# design.net
KiCad netlist of a schematic drawn in Altium Designer
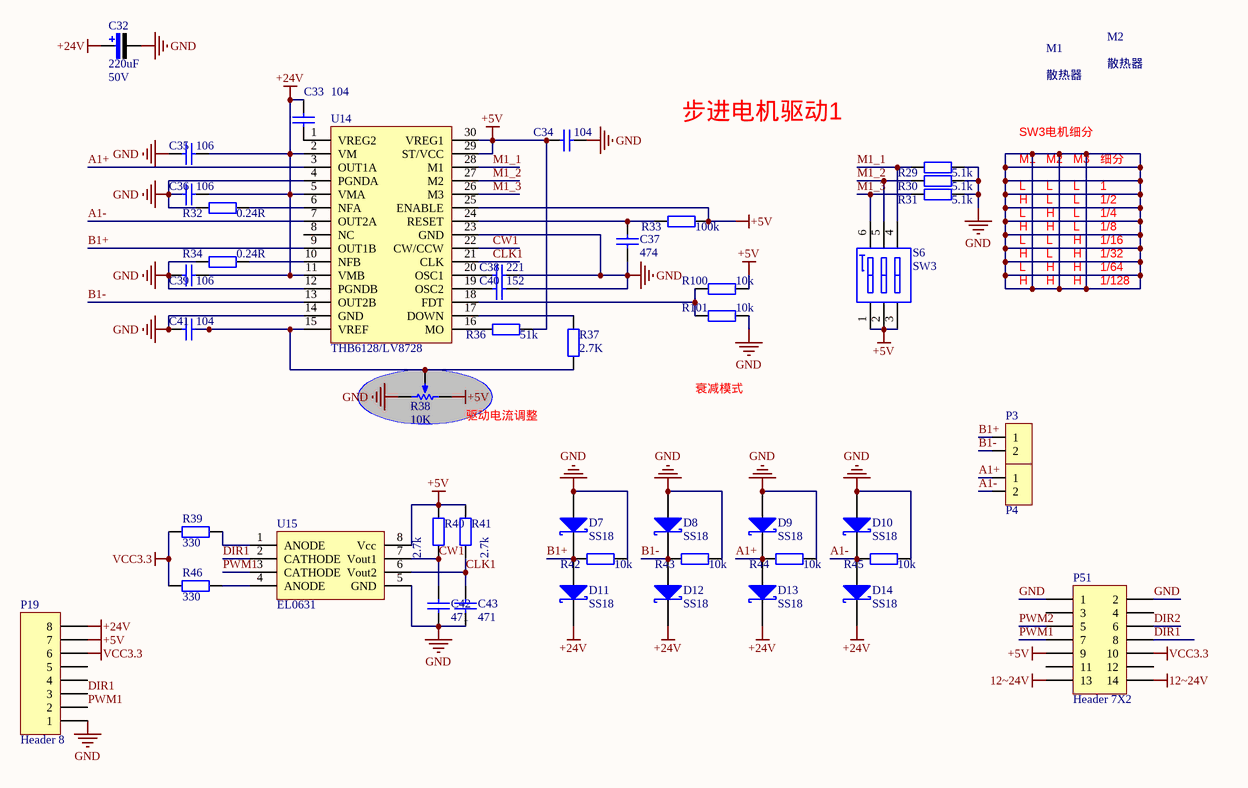
[diagram p0: 搅拌驱动驱动.SchDoc]

(export (version "E")
  (design (tool "Eeschema 10.0.6"))
  (components
    (comp (ref "C32")
      (value "220uF")
      (footprint "C-RB-S10")
      (description "极性电解电容")
      (fields
        (field (name "VOL") "50V")
        (field (name "Comment") "Cap Pol")
        (field (name "PUBLISHER") "Altium Limited")
      )
      (libsource (lib "Fszhang") (part "Cap Pol"))
    )
    (comp (ref "C33")
      (value "104")
      (footprint "C-RAD-0603")
      (description "无极性电容")
      (fields (field (name "Comment") "Cap") (field (name "PUBLISHER") "Altium Limited"))
      (libsource (lib "Fszhang") (part "Cap"))
    )
    (comp (ref "C34")
      (value "104")
      (footprint "C-RAD-0603")
      (description "无极性电容")
      (fields (field (name "Comment") "Cap") (field (name "PUBLISHER") "Altium Limited"))
      (libsource (lib "Fszhang") (part "Cap"))
    )
    (comp (ref "C35")
      (value "106")
      (footprint "C-RAD-0603")
      (description "无极性电容")
      (fields (field (name "Comment") "Cap") (field (name "PUBLISHER") "Altium Limited"))
      (libsource (lib "Fszhang") (part "Cap"))
    )
    (comp (ref "C36")
      (value "106")
      (footprint "C-RAD-0603")
      (description "无极性电容")
      (fields (field (name "Comment") "Cap") (field (name "PUBLISHER") "Altium Limited"))
      (libsource (lib "Fszhang") (part "Cap"))
    )
    (comp (ref "C37")
      (value "474")
      (footprint "C-RAD-0603")
      (description "无极性电容")
      (fields (field (name "Comment") "Cap") (field (name "PUBLISHER") "Altium Limited"))
      (libsource (lib "Fszhang") (part "Cap"))
    )
    (comp (ref "C38")
      (value "221")
      (footprint "C-RAD-0603")
      (description "无极性电容")
      (fields (field (name "Comment") "Cap") (field (name "PUBLISHER") "Altium Limited"))
      (libsource (lib "Fszhang") (part "Cap"))
    )
    (comp (ref "C39")
      (value "106")
      (footprint "C-RAD-0603")
      (description "无极性电容")
      (fields (field (name "Comment") "Cap") (field (name "PUBLISHER") "Altium Limited"))
      (libsource (lib "Fszhang") (part "Cap"))
    )
    (comp (ref "C40")
      (value "152")
      (footprint "C-RAD-0603")
      (description "无极性电容")
      (fields (field (name "Comment") "Cap") (field (name "PUBLISHER") "Altium Limited"))
      (libsource (lib "Fszhang") (part "Cap"))
    )
    (comp (ref "C41")
      (value "104")
      (footprint "C-RAD-0603")
      (description "无极性电容")
      (fields (field (name "Comment") "Cap") (field (name "PUBLISHER") "Altium Limited"))
      (libsource (lib "Fszhang") (part "Cap"))
    )
    (comp (ref "C42")
      (value "471")
      (footprint "C-RAD-0603")
      (description "无极性电容")
      (fields (field (name "Comment") "Cap") (field (name "PUBLISHER") "Altium Limited"))
      (libsource (lib "Fszhang") (part "Cap"))
    )
    (comp (ref "C43")
      (value "471")
      (footprint "C-RAD-0603")
      (description "无极性电容")
      (fields (field (name "Comment") "Cap") (field (name "PUBLISHER") "Altium Limited"))
      (libsource (lib "Fszhang") (part "Cap"))
    )
    (comp (ref "D7")
      (value "D-Schottky")
      (footprint "DIODE-SMA")
      (description "肖特基二极管")
      (fields (field (name "TYPE") "SS18") (field (name "PUBLISHER") "Altium Limited"))
      (libsource (lib "Fszhang") (part "D-Schottky"))
    )
    (comp (ref "D8")
      (value "D-Schottky")
      (footprint "DIODE-SMA")
      (description "肖特基二极管")
      (fields (field (name "TYPE") "SS18") (field (name "PUBLISHER") "Altium Limited"))
      (libsource (lib "Fszhang") (part "D-Schottky"))
    )
    (comp (ref "D9")
      (value "D-Schottky")
      (footprint "DIODE-SMA")
      (description "肖特基二极管")
      (fields (field (name "TYPE") "SS18") (field (name "PUBLISHER") "Altium Limited"))
      (libsource (lib "Fszhang") (part "D-Schottky"))
    )
    (comp (ref "D10")
      (value "D-Schottky")
      (footprint "DIODE-SMA")
      (description "肖特基二极管")
      (fields (field (name "TYPE") "SS18") (field (name "PUBLISHER") "Altium Limited"))
      (libsource (lib "Fszhang") (part "D-Schottky"))
    )
    (comp (ref "D11")
      (value "D-Schottky")
      (footprint "DIODE-SMA")
      (description "肖特基二极管")
      (fields (field (name "TYPE") "SS18") (field (name "PUBLISHER") "Altium Limited"))
      (libsource (lib "Fszhang") (part "D-Schottky"))
    )
    (comp (ref "D12")
      (value "D-Schottky")
      (footprint "DIODE-SMA")
      (description "肖特基二极管")
      (fields (field (name "TYPE") "SS18") (field (name "PUBLISHER") "Altium Limited"))
      (libsource (lib "Fszhang") (part "D-Schottky"))
    )
    (comp (ref "D13")
      (value "D-Schottky")
      (footprint "DIODE-SMA")
      (description "肖特基二极管")
      (fields (field (name "TYPE") "SS18") (field (name "PUBLISHER") "Altium Limited"))
      (libsource (lib "Fszhang") (part "D-Schottky"))
    )
    (comp (ref "D14")
      (value "D-Schottky")
      (footprint "DIODE-SMA")
      (description "肖特基二极管")
      (fields (field (name "TYPE") "SS18") (field (name "PUBLISHER") "Altium Limited"))
      (libsource (lib "Fszhang") (part "D-Schottky"))
    )
    (comp (ref "M1")
      (value "散热器")
      (footprint "26*26*10对角37.5")
      (description "26*26*10MM散热器孔距37MM")
      (libsource (lib "RADIATOR") (part "26*26*10散热器"))
    )
    (comp (ref "M2")
      (value "散热器")
      (footprint "26*26*10对角37.5")
      (description "26*26*10MM散热器孔距37MM")
      (libsource (lib "RADIATOR") (part "26*26*10散热器"))
    )
    (comp (ref "P3") (value "cnt2p") (footprint "接线端子5mm间距2p") (libsource (lib "MY_Library") (part "cnt2p")))
    (comp (ref "P4") (value "cnt2p") (footprint "接线端子5mm间距2p") (libsource (lib "MY_Library") (part "cnt2p")))
    (comp (ref "P19")
      (value "Header 8")
      (footprint "PH2.0-8P")
      (description "Header, 8-Pin")
      (fields (field (name "PUBLISHER") "Altium Limited"))
      (libsource (lib "Fszhang") (part "Header 8"))
    )
    (comp (ref "P51")
      (value "Header 7X2")
      (footprint "HDR7X2_A1")
      (description "Header, 7-Pin")
      (fields (field (name "PUBLISHER") "Altium Limited"))
      (libsource (lib "Fszhang") (part "Header 7X2"))
    )
    (comp (ref "R29")
      (value "5.1k")
      (footprint "0603-1")
      (description "贴片电阻")
      (fields (field (name "Comment") "Res1") (field (name "PUBLISHER") "Altium Limited"))
      (libsource (lib "Fszhang") (part "Res1"))
    )
    (comp (ref "R30")
      (value "5.1k")
      (footprint "0603-1")
      (description "贴片电阻")
      (fields (field (name "Comment") "Res1") (field (name "PUBLISHER") "Altium Limited"))
      (libsource (lib "Fszhang") (part "Res1"))
    )
    (comp (ref "R31")
      (value "5.1k")
      (footprint "0603-1")
      (description "贴片电阻")
      (fields (field (name "Comment") "Res1") (field (name "PUBLISHER") "Altium Limited"))
      (libsource (lib "Fszhang") (part "Res1"))
    )
    (comp (ref "R32")
      (value "0.24R")
      (footprint "2512")
      (description "贴片电阻")
      (fields (field (name "Comment") "Res1") (field (name "PUBLISHER") "Altium Limited"))
      (libsource (lib "Fszhang") (part "Res1"))
    )
    (comp (ref "R33")
      (value "100k")
      (footprint "0603-1")
      (description "贴片电阻")
      (fields (field (name "Comment") "Res1") (field (name "PUBLISHER") "Altium Limited"))
      (libsource (lib "Fszhang") (part "Res1"))
    )
    (comp (ref "R34")
      (value "0.24R")
      (footprint "2512")
      (description "贴片电阻")
      (fields (field (name "Comment") "Res1") (field (name "PUBLISHER") "Altium Limited"))
      (libsource (lib "") (part "Res1_1"))
    )
    (comp (ref "R36")
      (value "51k")
      (footprint "0603-1")
      (description "贴片电阻")
      (fields (field (name "Comment") "Res1") (field (name "PUBLISHER") "Altium Limited"))
      (libsource (lib "Fszhang") (part "Res1"))
    )
    (comp (ref "R37")
      (value "2.7K")
      (footprint "0603-1")
      (description "贴片电阻")
      (fields (field (name "Comment") "Res1") (field (name "PUBLISHER") "Altium Limited"))
      (libsource (lib "") (part "Res1_3"))
    )
    (comp (ref "R38")
      (value "10K")
      (footprint "VR-3266W")
      (description "精密可调电阻")
      (fields (field (name "Comment") "RPot") (field (name "PUBLISHER") "Altium Limited"))
      (libsource (lib "Fszhang") (part "RPot"))
    )
    (comp (ref "R39")
      (value "330")
      (footprint "0603-1")
      (description "贴片电阻")
      (fields (field (name "Comment") "Res1") (field (name "PUBLISHER") "Altium Limited"))
      (libsource (lib "") (part "Res1_1"))
    )
    (comp (ref "R40")
      (value "2.7k")
      (footprint "0603-1")
      (description "贴片电阻")
      (fields (field (name "Comment") "Res1") (field (name "PUBLISHER") "Altium Limited"))
      (libsource (lib "") (part "Res1_2"))
    )
    (comp (ref "R41")
      (value "2.7k")
      (footprint "0603-1")
      (description "贴片电阻")
      (fields (field (name "Comment") "Res1") (field (name "PUBLISHER") "Altium Limited"))
      (libsource (lib "") (part "Res1_2"))
    )
    (comp (ref "R42")
      (value "10k")
      (footprint "0603-1")
      (description "贴片电阻")
      (fields (field (name "Comment") "Res1") (field (name "PUBLISHER") "Altium Limited"))
      (libsource (lib "Fszhang") (part "Res1"))
    )
    (comp (ref "R43")
      (value "10k")
      (footprint "0603-1")
      (description "贴片电阻")
      (fields (field (name "Comment") "Res1") (field (name "PUBLISHER") "Altium Limited"))
      (libsource (lib "Fszhang") (part "Res1"))
    )
    (comp (ref "R44")
      (value "10k")
      (footprint "0603-1")
      (description "贴片电阻")
      (fields (field (name "Comment") "Res1") (field (name "PUBLISHER") "Altium Limited"))
      (libsource (lib "Fszhang") (part "Res1"))
    )
    (comp (ref "R45")
      (value "10k")
      (footprint "0603-1")
      (description "贴片电阻")
      (fields (field (name "Comment") "Res1") (field (name "PUBLISHER") "Altium Limited"))
      (libsource (lib "Fszhang") (part "Res1"))
    )
    (comp (ref "R46")
      (value "330")
      (footprint "0603-1")
      (description "贴片电阻")
      (fields (field (name "Comment") "Res1") (field (name "PUBLISHER") "Altium Limited"))
      (libsource (lib "") (part "Res1_1"))
    )
    (comp (ref "R100")
      (value "10k")
      (footprint "0603-1")
      (description "贴片电阻")
      (fields (field (name "Comment") "Res1") (field (name "PUBLISHER") "Altium Limited"))
      (libsource (lib "Fszhang") (part "Res1"))
    )
    (comp (ref "R101")
      (value "10k")
      (footprint "0603-1")
      (description "贴片电阻")
      (fields (field (name "Comment") "Res1") (field (name "PUBLISHER") "Altium Limited"))
      (libsource (lib "Fszhang") (part "Res1"))
    )
    (comp (ref "S6")
      (value "SW3")
      (footprint "SW6_3BIT")
      (description "3位编码开关")
      (libsource (lib "Fszhang") (part "SW3"))
    )
    (comp (ref "U14")
      (value "THB6128/LV8728")
      (footprint "SIOC-30-W")
      (description "步进电机驱动")
      (libsource (lib "Fszhang") (part "THB6128"))
    )
    (comp (ref "U15")
      (value "EL0631")
      (footprint "EL0631")
      (description "双路隔离光耦")
      (libsource (lib "Fszhang") (part "EL0631"))
    )
  )
  (nets
    (net (code "1") (name "+5V") (class "Default")
      (node (ref "C34") (pin "1") (pinfunction "1_1") (pintype "passive"))
      (node (ref "P19") (pin "7") (pinfunction "7_7") (pintype "passive"))
      (node (ref "P51") (pin "9") (pinfunction "9_9") (pintype "passive"))
      (node (ref "R100") (pin "2") (pinfunction "2_2") (pintype "passive"))
      (node (ref "R33") (pin "2") (pinfunction "2_2") (pintype "passive"))
      (node (ref "R36") (pin "2") (pinfunction "2_2") (pintype "passive"))
      (node (ref "R38") (pin "1") (pinfunction "TOP_1") (pintype "passive"))
      (node (ref "R40") (pin "2") (pinfunction "2_2") (pintype "passive"))
      (node (ref "R41") (pin "2") (pinfunction "2_2") (pintype "passive"))
      (node (ref "S6") (pin "1") (pinfunction "1_1") (pintype "passive"))
      (node (ref "S6") (pin "2") (pinfunction "2_2") (pintype "passive"))
      (node (ref "S6") (pin "3") (pinfunction "3_3") (pintype "passive"))
      (node (ref "U14") (pin "25") (pinfunction "ENABLE_25") (pintype "passive"))
      (node (ref "U14") (pin "29") (pinfunction "ST/VCC_29") (pintype "passive"))
      (node (ref "U14") (pin "30") (pinfunction "VREG1_30") (pintype "passive"))
      (node (ref "U15") (pin "8") (pinfunction "Vcc_8") (pintype "passive"))
    )
    (net (code "2") (name "+24V") (class "Default")
      (node (ref "C32") (pin "1") (pinfunction "1_1") (pintype "passive"))
      (node (ref "C33") (pin "1") (pinfunction "1_1") (pintype "passive"))
      (node (ref "C35") (pin "2") (pinfunction "2_2") (pintype "passive"))
      (node (ref "C36") (pin "2") (pinfunction "2_2") (pintype "passive"))
      (node (ref "C39") (pin "2") (pinfunction "2_2") (pintype "passive"))
      (node (ref "D11") (pin "2") (pinfunction "K_2") (pintype "passive"))
      (node (ref "D12") (pin "2") (pinfunction "K_2") (pintype "passive"))
      (node (ref "D13") (pin "2") (pinfunction "K_2") (pintype "passive"))
      (node (ref "D14") (pin "2") (pinfunction "K_2") (pintype "passive"))
      (node (ref "P19") (pin "8") (pinfunction "8_8") (pintype "passive"))
      (node (ref "U14") (pin "11") (pinfunction "VMB_11") (pintype "passive"))
      (node (ref "U14") (pin "2") (pinfunction "VM_2") (pintype "passive"))
      (node (ref "U14") (pin "5") (pinfunction "VMA_5") (pintype "passive"))
    )
    (net (code "3") (name "/A1+") (class "Default")
      (node (ref "D13") (pin "1") (pinfunction "A_1") (pintype "passive"))
      (node (ref "D9") (pin "2") (pinfunction "K_2") (pintype "passive"))
      (node (ref "P4") (pin "1") (pinfunction "1_1") (pintype "passive"))
      (node (ref "R44") (pin "1") (pinfunction "1_1") (pintype "passive"))
      (node (ref "U14") (pin "3") (pinfunction "OUT1A_3") (pintype "passive"))
    )
    (net (code "4") (name "/A1-") (class "Default")
      (node (ref "D10") (pin "2") (pinfunction "K_2") (pintype "passive"))
      (node (ref "D14") (pin "1") (pinfunction "A_1") (pintype "passive"))
      (node (ref "P4") (pin "2") (pinfunction "2_2") (pintype "passive"))
      (node (ref "R45") (pin "1") (pinfunction "1_1") (pintype "passive"))
      (node (ref "U14") (pin "7") (pinfunction "OUT2A_7") (pintype "passive"))
    )
    (net (code "5") (name "/B1+") (class "Default")
      (node (ref "D11") (pin "1") (pinfunction "A_1") (pintype "passive"))
      (node (ref "D7") (pin "2") (pinfunction "K_2") (pintype "passive"))
      (node (ref "P3") (pin "1") (pinfunction "1_1") (pintype "passive"))
      (node (ref "R42") (pin "1") (pinfunction "1_1") (pintype "passive"))
      (node (ref "U14") (pin "9") (pinfunction "OUT1B_9") (pintype "passive"))
    )
    (net (code "6") (name "/B1-") (class "Default")
      (node (ref "D12") (pin "1") (pinfunction "A_1") (pintype "passive"))
      (node (ref "D8") (pin "2") (pinfunction "K_2") (pintype "passive"))
      (node (ref "P3") (pin "2") (pinfunction "2_2") (pintype "passive"))
      (node (ref "R43") (pin "1") (pinfunction "1_1") (pintype "passive"))
      (node (ref "U14") (pin "13") (pinfunction "OUT2B_13") (pintype "passive"))
    )
    (net (code "7") (name "/CLK1") (class "Default")
      (node (ref "C43") (pin "2") (pinfunction "2_2") (pintype "passive"))
      (node (ref "R41") (pin "1") (pinfunction "1_1") (pintype "passive"))
      (node (ref "U14") (pin "21") (pinfunction "CLK_21") (pintype "passive"))
      (node (ref "U15") (pin "6") (pinfunction "Vout2_6") (pintype "passive"))
    )
    (net (code "8") (name "/CW1") (class "Default")
      (node (ref "C42") (pin "2") (pinfunction "2_2") (pintype "passive"))
      (node (ref "R40") (pin "1") (pinfunction "1_1") (pintype "passive"))
      (node (ref "U14") (pin "22") (pinfunction "CW/CCW_22") (pintype "passive"))
      (node (ref "U15") (pin "7") (pinfunction "Vout1_7") (pintype "passive"))
    )
    (net (code "9") (name "/DIR1") (class "Default")
      (node (ref "P19") (pin "3") (pinfunction "3_3") (pintype "passive"))
      (node (ref "P51") (pin "8") (pinfunction "8_8") (pintype "passive"))
      (node (ref "U15") (pin "2") (pinfunction "CATHODE_2") (pintype "passive"))
    )
    (net (code "10") (name "/DIR2") (class "Default")
      (node (ref "P51") (pin "6") (pinfunction "6_6") (pintype "passive"))
    )
    (net (code "11") (name "/M1_1") (class "Default")
      (node (ref "R29") (pin "1") (pinfunction "1_1") (pintype "passive"))
      (node (ref "S6") (pin "4") (pinfunction "4_4") (pintype "passive"))
      (node (ref "U14") (pin "28") (pinfunction "M1_28") (pintype "passive"))
    )
    (net (code "12") (name "/M1_2") (class "Default")
      (node (ref "R30") (pin "1") (pinfunction "1_1") (pintype "passive"))
      (node (ref "S6") (pin "5") (pinfunction "5_5") (pintype "passive"))
      (node (ref "U14") (pin "27") (pinfunction "M2_27") (pintype "passive"))
    )
    (net (code "13") (name "/M1_3") (class "Default")
      (node (ref "R31") (pin "1") (pinfunction "1_1") (pintype "passive"))
      (node (ref "S6") (pin "6") (pinfunction "6_6") (pintype "passive"))
      (node (ref "U14") (pin "26") (pinfunction "M3_26") (pintype "passive"))
    )
    (net (code "14") (name "/PWM1") (class "Default")
      (node (ref "P19") (pin "2") (pinfunction "2_2") (pintype "passive"))
      (node (ref "P51") (pin "7") (pinfunction "7_7") (pintype "passive"))
      (node (ref "U15") (pin "3") (pinfunction "CATHODE_3") (pintype "passive"))
    )
    (net (code "15") (name "/PWM2") (class "Default")
      (node (ref "P51") (pin "5") (pinfunction "5_5") (pintype "passive"))
    )
    (net (code "16") (name "12~24V") (class "Default")
      (node (ref "P51") (pin "13") (pinfunction "13_13") (pintype "passive"))
      (node (ref "P51") (pin "14") (pinfunction "14_14") (pintype "passive"))
    )
    (net (code "17") (name "GND") (class "Default")
      (node (ref "C32") (pin "2") (pinfunction "2_2") (pintype "passive"))
      (node (ref "C34") (pin "2") (pinfunction "2_2") (pintype "passive"))
      (node (ref "C35") (pin "1") (pinfunction "1_1") (pintype "passive"))
      (node (ref "C36") (pin "1") (pinfunction "1_1") (pintype "passive"))
      (node (ref "C37") (pin "1") (pinfunction "1_1") (pintype "passive"))
      (node (ref "C38") (pin "2") (pinfunction "2_2") (pintype "passive"))
      (node (ref "C39") (pin "1") (pinfunction "1_1") (pintype "passive"))
      (node (ref "C40") (pin "2") (pinfunction "2_2") (pintype "passive"))
      (node (ref "C41") (pin "1") (pinfunction "1_1") (pintype "passive"))
      (node (ref "C42") (pin "1") (pinfunction "1_1") (pintype "passive"))
      (node (ref "C43") (pin "1") (pinfunction "1_1") (pintype "passive"))
      (node (ref "D10") (pin "1") (pinfunction "A_1") (pintype "passive"))
      (node (ref "D7") (pin "1") (pinfunction "A_1") (pintype "passive"))
      (node (ref "D8") (pin "1") (pinfunction "A_1") (pintype "passive"))
      (node (ref "D9") (pin "1") (pinfunction "A_1") (pintype "passive"))
      (node (ref "P19") (pin "1") (pinfunction "1_1") (pintype "passive"))
      (node (ref "P51") (pin "1") (pinfunction "1_1") (pintype "passive"))
      (node (ref "P51") (pin "2") (pinfunction "2_2") (pintype "passive"))
      (node (ref "R101") (pin "2") (pinfunction "2_2") (pintype "passive"))
      (node (ref "R29") (pin "2") (pinfunction "2_2") (pintype "passive"))
      (node (ref "R30") (pin "2") (pinfunction "2_2") (pintype "passive"))
      (node (ref "R31") (pin "2") (pinfunction "2_2") (pintype "passive"))
      (node (ref "R32") (pin "1") (pinfunction "1_1") (pintype "passive"))
      (node (ref "R34") (pin "2") (pinfunction "2_2") (pintype "passive"))
      (node (ref "R38") (pin "3") (pinfunction "BOT_3") (pintype "passive"))
      (node (ref "R42") (pin "2") (pinfunction "2_2") (pintype "passive"))
      (node (ref "R43") (pin "2") (pinfunction "2_2") (pintype "passive"))
      (node (ref "R44") (pin "2") (pinfunction "2_2") (pintype "passive"))
      (node (ref "R45") (pin "2") (pinfunction "2_2") (pintype "passive"))
      (node (ref "U14") (pin "12") (pinfunction "PGNDB_12") (pintype "passive"))
      (node (ref "U14") (pin "14") (pinfunction "GND_14") (pintype "passive"))
      (node (ref "U14") (pin "23") (pinfunction "GND_23") (pintype "passive"))
      (node (ref "U14") (pin "4") (pinfunction "PGNDA_4") (pintype "passive"))
      (node (ref "U15") (pin "5") (pinfunction "GND_5") (pintype "passive"))
    )
    (net (code "18") (name "Net-(R38-TAP)") (class "Default")
      (node (ref "C41") (pin "2") (pinfunction "2_2") (pintype "passive"))
      (node (ref "R37") (pin "2") (pinfunction "2_2") (pintype "passive"))
      (node (ref "R38") (pin "2") (pinfunction "TAP_2") (pintype "passive"))
      (node (ref "U14") (pin "15") (pinfunction "VREF_15") (pintype "passive"))
    )
    (net (code "19") (name "Net-(R39-Pad1)") (class "Default")
      (node (ref "R39") (pin "1") (pinfunction "1_1") (pintype "passive"))
      (node (ref "U15") (pin "1") (pinfunction "ANODE_1") (pintype "passive"))
    )
    (net (code "20") (name "Net-(R46-Pad1)") (class "Default")
      (node (ref "R46") (pin "1") (pinfunction "1_1") (pintype "passive"))
      (node (ref "U15") (pin "4") (pinfunction "ANODE_4") (pintype "passive"))
    )
    (net (code "21") (name "Net-(U14-DOWN)") (class "Default")
      (node (ref "R37") (pin "1") (pinfunction "1_1") (pintype "passive"))
      (node (ref "U14") (pin "17") (pinfunction "DOWN_17") (pintype "passive"))
    )
    (net (code "22") (name "Net-(U14-FDT)") (class "Default")
      (node (ref "R100") (pin "1") (pinfunction "1_1") (pintype "passive"))
      (node (ref "R101") (pin "1") (pinfunction "1_1") (pintype "passive"))
      (node (ref "U14") (pin "18") (pinfunction "FDT_18") (pintype "passive"))
    )
    (net (code "23") (name "Net-(U14-MO)") (class "Default")
      (node (ref "R36") (pin "1") (pinfunction "1_1") (pintype "passive"))
      (node (ref "U14") (pin "16") (pinfunction "MO_16") (pintype "passive"))
    )
    (net (code "24") (name "Net-(U14-NFA)") (class "Default")
      (node (ref "R32") (pin "2") (pinfunction "2_2") (pintype "passive"))
      (node (ref "U14") (pin "6") (pinfunction "NFA_6") (pintype "passive"))
    )
    (net (code "25") (name "Net-(U14-NFB)") (class "Default")
      (node (ref "R34") (pin "1") (pinfunction "1_1") (pintype "passive"))
      (node (ref "U14") (pin "10") (pinfunction "NFB_10") (pintype "passive"))
    )
    (net (code "26") (name "Net-(U14-OSC1)") (class "Default")
      (node (ref "C38") (pin "1") (pinfunction "1_1") (pintype "passive"))
      (node (ref "U14") (pin "20") (pinfunction "OSC1_20") (pintype "passive"))
    )
    (net (code "27") (name "Net-(U14-OSC2)") (class "Default")
      (node (ref "C40") (pin "1") (pinfunction "1_1") (pintype "passive"))
      (node (ref "U14") (pin "19") (pinfunction "OSC2_19") (pintype "passive"))
    )
    (net (code "28") (name "Net-(U14-RESET)") (class "Default")
      (node (ref "C37") (pin "2") (pinfunction "2_2") (pintype "passive"))
      (node (ref "R33") (pin "1") (pinfunction "1_1") (pintype "passive"))
      (node (ref "U14") (pin "24") (pinfunction "RESET_24") (pintype "passive"))
    )
    (net (code "29") (name "Net-(U14-VREG2)") (class "Default")
      (node (ref "C33") (pin "2") (pinfunction "2_2") (pintype "passive"))
      (node (ref "U14") (pin "1") (pinfunction "VREG2_1") (pintype "passive"))
    )
    (net (code "30") (name "VCC3.3") (class "Default")
      (node (ref "P19") (pin "6") (pinfunction "6_6") (pintype "passive"))
      (node (ref "P51") (pin "10") (pinfunction "10_10") (pintype "passive"))
      (node (ref "R39") (pin "2") (pinfunction "2_2") (pintype "passive"))
      (node (ref "R46") (pin "2") (pinfunction "2_2") (pintype "passive"))
    )
    (net (code "31") (name "unconnected-(P19-Pad4)") (class "Default")
      (node (ref "P19") (pin "4") (pinfunction "4_4") (pintype "passive"))
    )
    (net (code "32") (name "unconnected-(P19-Pad5)") (class "Default")
      (node (ref "P19") (pin "5") (pinfunction "5_5") (pintype "passive"))
    )
    (net (code "33") (name "unconnected-(P51-Pad3)") (class "Default")
      (node (ref "P51") (pin "3") (pinfunction "3_3") (pintype "passive"))
    )
    (net (code "34") (name "unconnected-(P51-Pad4)") (class "Default")
      (node (ref "P51") (pin "4") (pinfunction "4_4") (pintype "passive"))
    )
    (net (code "35") (name "unconnected-(P51-Pad11)") (class "Default")
      (node (ref "P51") (pin "11") (pinfunction "11_11") (pintype "passive"))
    )
    (net (code "36") (name "unconnected-(P51-Pad12)") (class "Default")
      (node (ref "P51") (pin "12") (pinfunction "12_12") (pintype "passive"))
    )
    (net (code "37") (name "unconnected-(U14-NC-Pad8)") (class "Default")
      (node (ref "U14") (pin "8") (pinfunction "NC_8") (pintype "passive"))
    )
  )
)
